# Arduino_Shield.net
KiCad netlist of a schematic drawn in EAGLE
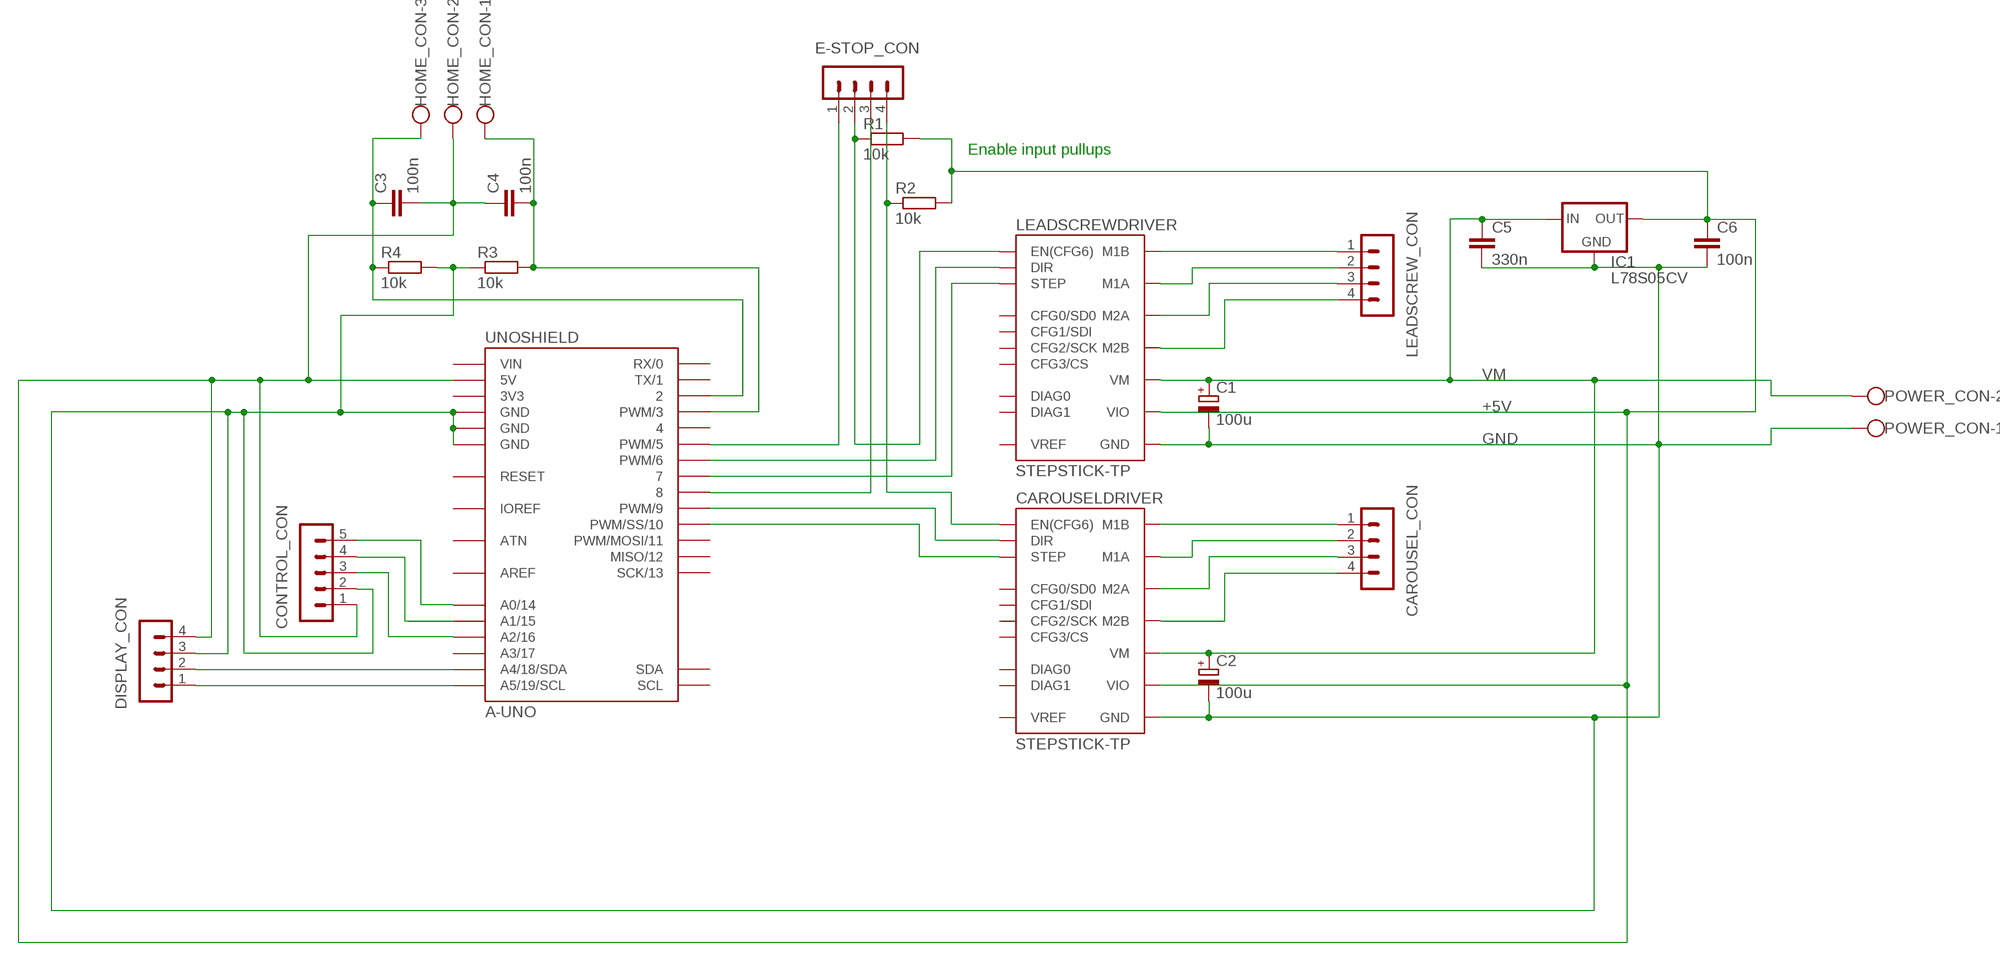
[diagram p0: schematic, sheet 1]

(export (version "E")
  (design (tool "Eeschema 10.0.6"))
  (components
    (comp (ref "C1")
      (value "100u")
      (footprint "eagle-import:E3,5-8")
      (libsource (lib "eagle-import") (part "CPOL-EUE3.5-8"))
    )
    (comp (ref "C2")
      (value "100u")
      (footprint "eagle-import:E3,5-8")
      (libsource (lib "eagle-import") (part "CPOL-EUE3.5-8"))
    )
    (comp (ref "C3")
      (value "100n")
      (footprint "eagle-import:C025-024X044")
      (libsource (lib "eagle-import") (part "C-EU025-024X044"))
    )
    (comp (ref "C4")
      (value "100n")
      (footprint "eagle-import:C025-024X044")
      (libsource (lib "eagle-import") (part "C-EU025-024X044"))
    )
    (comp (ref "C5")
      (value "330n")
      (footprint "eagle-import:C025-030X050")
      (libsource (lib "eagle-import") (part "C-EU025-030X050"))
    )
    (comp (ref "C6")
      (value "100n")
      (footprint "eagle-import:C025-030X050")
      (libsource (lib "eagle-import") (part "C-EU025-030X050"))
    )
    (comp (ref "CAROUSELDRIVER")
      (value "STEPSTICK-TP")
      (footprint "eagle-import:STEPSTICK_TP")
      (libsource (lib "eagle-import") (part "STEPSTICK-TP"))
    )
    (comp (ref "CAROUSEL_CON")
      (value "MA04-1")
      (footprint "eagle-import:MA04-1")
      (libsource (lib "eagle-import") (part "MA04-1"))
    )
    (comp (ref "CONTROL_CON")
      (value "MA05-1")
      (footprint "eagle-import:MA05-1")
      (libsource (lib "eagle-import") (part "MA05-1"))
    )
    (comp (ref "DISPLAY_CON")
      (value "MA04-1")
      (footprint "eagle-import:MA04-1")
      (libsource (lib "eagle-import") (part "MA04-1"))
    )
    (comp (ref "E-STOP_CON")
      (value "MA04-1")
      (footprint "eagle-import:MA04-1")
      (libsource (lib "eagle-import") (part "MA04-1"))
    )
    (comp (ref "HOME_CON")
      (value "W237-103")
      (footprint "eagle-import:W237-103")
      (fields (field (name "MPN") "237-103"))
      (libsource (lib "eagle-import") (part "W237-103"))
    )
    (comp (ref "IC1")
      (value "L78S05CV")
      (footprint "eagle-import:TO-220-STANDING")
      (fields (field (name "MF") "STMicroelectronics"))
      (libsource (lib "eagle-import") (part "L78S05CV"))
    )
    (comp (ref "LEADSCREWDRIVER")
      (value "STEPSTICK-TP")
      (footprint "eagle-import:STEPSTICK_TP")
      (libsource (lib "eagle-import") (part "STEPSTICK-TP"))
    )
    (comp (ref "LEADSCREW_CON")
      (value "MA04-1")
      (footprint "eagle-import:MA04-1")
      (libsource (lib "eagle-import") (part "MA04-1"))
    )
    (comp (ref "POWER_CON")
      (value "W237-102")
      (footprint "eagle-import:W237-102")
      (fields (field (name "MPN") "237-102"))
      (libsource (lib "eagle-import") (part "W237-102"))
    )
    (comp (ref "R1")
      (value "10k")
      (footprint "eagle-import:0207_12")
      (libsource (lib "eagle-import") (part "R-EU_0207/12"))
    )
    (comp (ref "R2")
      (value "10k")
      (footprint "eagle-import:0207_12")
      (libsource (lib "eagle-import") (part "R-EU_0207/12"))
    )
    (comp (ref "R3")
      (value "10k")
      (footprint "eagle-import:0207_10")
      (libsource (lib "eagle-import") (part "R-EU_0207/10"))
    )
    (comp (ref "R4")
      (value "10k")
      (footprint "eagle-import:0207_10")
      (libsource (lib "eagle-import") (part "R-EU_0207/10"))
    )
    (comp (ref "UNOSHIELD")
      (value "A-UNO")
      (footprint "eagle-import:A-UNO")
      (libsource (lib "eagle-import") (part "A-UNO"))
    )
  )
  (nets
    (net (code "1") (name "/+5V") (class "Default")
      (node (ref "C3") (pin "2") (pinfunction "2_2") (pintype "passive"))
      (node (ref "C4") (pin "1") (pinfunction "1_1") (pintype "passive"))
      (node (ref "C6") (pin "1") (pinfunction "1_1") (pintype "passive"))
      (node (ref "CAROUSELDRIVER") (pin "VIO") (pinfunction "VIO_VIO") (pintype "power_in"))
      (node (ref "CONTROL_CON") (pin "1") (pinfunction "1_1") (pintype "passive"))
      (node (ref "DISPLAY_CON") (pin "4") (pinfunction "4_4") (pintype "passive"))
      (node (ref "HOME_CON") (pin "2") (pinfunction "KL_2") (pintype "passive"))
      (node (ref "IC1") (pin "3") (pinfunction "OUT_3") (pintype "passive"))
      (node (ref "LEADSCREWDRIVER") (pin "VIO") (pinfunction "VIO_VIO") (pintype "power_in"))
      (node (ref "R1") (pin "2") (pinfunction "2_2") (pintype "passive"))
      (node (ref "R2") (pin "2") (pinfunction "2_2") (pintype "passive"))
      (node (ref "UNOSHIELD") (pin "5V") (pinfunction "5V_5V") (pintype "power_in"))
    )
    (net (code "2") (name "/3V3") (class "Default")
      (node (ref "UNOSHIELD") (pin "3V3") (pinfunction "3V3_3V3") (pintype "power_in"))
    )
    (net (code "3") (name "/AREF") (class "Default")
      (node (ref "UNOSHIELD") (pin "AREF") (pinfunction "AREF_AREF") (pintype "power_in"))
    )
    (net (code "4") (name "/GND") (class "Default")
      (node (ref "C1") (pin "-") (pinfunction "-_-") (pintype "passive"))
      (node (ref "C2") (pin "-") (pinfunction "-_-") (pintype "passive"))
      (node (ref "C5") (pin "2") (pinfunction "2_2") (pintype "passive"))
      (node (ref "C6") (pin "2") (pinfunction "2_2") (pintype "passive"))
      (node (ref "CAROUSELDRIVER") (pin "GND@1") (pinfunction "GND_GND@1") (pintype "power_in"))
      (node (ref "CAROUSELDRIVER") (pin "GND@2") (pinfunction "GND_GND@2") (pintype "power_in"))
      (node (ref "CONTROL_CON") (pin "2") (pinfunction "2_2") (pintype "passive"))
      (node (ref "DISPLAY_CON") (pin "3") (pinfunction "3_3") (pintype "passive"))
      (node (ref "IC1") (pin "2") (pinfunction "GND_2") (pintype "input"))
      (node (ref "LEADSCREWDRIVER") (pin "GND@1") (pinfunction "GND_GND@1") (pintype "power_in"))
      (node (ref "LEADSCREWDRIVER") (pin "GND@2") (pinfunction "GND_GND@2") (pintype "power_in"))
      (node (ref "POWER_CON") (pin "1") (pinfunction "KL_1") (pintype "passive"))
      (node (ref "R3") (pin "1") (pinfunction "1_1") (pintype "passive"))
      (node (ref "R4") (pin "2") (pinfunction "2_2") (pintype "passive"))
      (node (ref "UNOSHIELD") (pin "GND@1") (pinfunction "GND_GND@1") (pintype "power_in"))
      (node (ref "UNOSHIELD") (pin "GND@2") (pinfunction "GND_GND@2") (pintype "power_in"))
      (node (ref "UNOSHIELD") (pin "GND@3") (pinfunction "GND_GND@3") (pintype "power_in"))
    )
    (net (code "5") (name "/IOREF") (class "Default")
      (node (ref "UNOSHIELD") (pin "IOREF") (pinfunction "IOREF_IOREF") (pintype "power_in"))
    )
    (net (code "6") (name "/VIN") (class "Default")
      (node (ref "UNOSHIELD") (pin "VIN") (pinfunction "VIN_VIN") (pintype "power_in"))
    )
    (net (code "7") (name "/VM") (class "Default")
      (node (ref "C1") (pin "+") (pinfunction "+_+") (pintype "passive"))
      (node (ref "C2") (pin "+") (pinfunction "+_+") (pintype "passive"))
      (node (ref "C5") (pin "1") (pinfunction "1_1") (pintype "passive"))
      (node (ref "CAROUSELDRIVER") (pin "VM") (pinfunction "VM_VM") (pintype "power_in"))
      (node (ref "IC1") (pin "1") (pinfunction "IN_1") (pintype "input"))
      (node (ref "LEADSCREWDRIVER") (pin "VM") (pinfunction "VM_VM") (pintype "power_in"))
      (node (ref "POWER_CON") (pin "2") (pinfunction "KL_2") (pintype "passive"))
    )
    (net (code "8") (name "Net-(CAROUSELDRIVER-EN(CFG6))") (class "Default")
      (node (ref "CAROUSELDRIVER") (pin "EN") (pinfunction "EN(CFG6)_EN") (pintype "bidirectional"))
      (node (ref "E-STOP_CON") (pin "4") (pinfunction "4_4") (pintype "passive"))
      (node (ref "R2") (pin "1") (pinfunction "1_1") (pintype "passive"))
    )
    (net (code "9") (name "Net-(CAROUSELDRIVER-PadM1A)") (class "Default")
      (node (ref "CAROUSELDRIVER") (pin "M1A") (pinfunction "M1A_M1A") (pintype "output"))
      (node (ref "CAROUSEL_CON") (pin "2") (pinfunction "2_2") (pintype "passive"))
    )
    (net (code "10") (name "Net-(CAROUSELDRIVER-PadM1B)") (class "Default")
      (node (ref "CAROUSELDRIVER") (pin "M1B") (pinfunction "M1B_M1B") (pintype "output"))
      (node (ref "CAROUSEL_CON") (pin "1") (pinfunction "1_1") (pintype "passive"))
    )
    (net (code "11") (name "Net-(CAROUSELDRIVER-PadM2A)") (class "Default")
      (node (ref "CAROUSELDRIVER") (pin "M2A") (pinfunction "M2A_M2A") (pintype "output"))
      (node (ref "CAROUSEL_CON") (pin "3") (pinfunction "3_3") (pintype "passive"))
    )
    (net (code "12") (name "Net-(CAROUSELDRIVER-PadM2B)") (class "Default")
      (node (ref "CAROUSELDRIVER") (pin "M2B") (pinfunction "M2B_M2B") (pintype "output"))
      (node (ref "CAROUSEL_CON") (pin "4") (pinfunction "4_4") (pintype "passive"))
    )
    (net (code "13") (name "Net-(E-STOP_CON-Pad3)") (class "Default")
      (node (ref "E-STOP_CON") (pin "3") (pinfunction "3_3") (pintype "passive"))
      (node (ref "UNOSHIELD") (pin "8") (pinfunction "8_8") (pintype "bidirectional"))
    )
    (net (code "14") (name "Net-(HOME_CONA-KL)") (class "Default")
      (node (ref "C4") (pin "2") (pinfunction "2_2") (pintype "passive"))
      (node (ref "HOME_CON") (pin "1") (pinfunction "KL_1") (pintype "passive"))
      (node (ref "R3") (pin "2") (pinfunction "2_2") (pintype "passive"))
      (node (ref "UNOSHIELD") (pin "3") (pinfunction "PWM/3_3") (pintype "bidirectional"))
    )
    (net (code "15") (name "Net-(HOME_CONC-KL)") (class "Default")
      (node (ref "C3") (pin "1") (pinfunction "1_1") (pintype "passive"))
      (node (ref "HOME_CON") (pin "3") (pinfunction "KL_3") (pintype "passive"))
      (node (ref "R4") (pin "1") (pinfunction "1_1") (pintype "passive"))
      (node (ref "UNOSHIELD") (pin "2") (pinfunction "2_2") (pintype "bidirectional"))
    )
    (net (code "16") (name "Net-(LEADSCREWDRIVER-EN(CFG6))") (class "Default")
      (node (ref "E-STOP_CON") (pin "2") (pinfunction "2_2") (pintype "passive"))
      (node (ref "LEADSCREWDRIVER") (pin "EN") (pinfunction "EN(CFG6)_EN") (pintype "bidirectional"))
      (node (ref "R1") (pin "1") (pinfunction "1_1") (pintype "passive"))
    )
    (net (code "17") (name "Net-(LEADSCREWDRIVER-PadM1A)") (class "Default")
      (node (ref "LEADSCREWDRIVER") (pin "M1A") (pinfunction "M1A_M1A") (pintype "output"))
      (node (ref "LEADSCREW_CON") (pin "2") (pinfunction "2_2") (pintype "passive"))
    )
    (net (code "18") (name "Net-(LEADSCREWDRIVER-PadM1B)") (class "Default")
      (node (ref "LEADSCREWDRIVER") (pin "M1B") (pinfunction "M1B_M1B") (pintype "output"))
      (node (ref "LEADSCREW_CON") (pin "1") (pinfunction "1_1") (pintype "passive"))
    )
    (net (code "19") (name "Net-(LEADSCREWDRIVER-PadM2A)") (class "Default")
      (node (ref "LEADSCREWDRIVER") (pin "M2A") (pinfunction "M2A_M2A") (pintype "output"))
      (node (ref "LEADSCREW_CON") (pin "3") (pinfunction "3_3") (pintype "passive"))
    )
    (net (code "20") (name "Net-(LEADSCREWDRIVER-PadM2B)") (class "Default")
      (node (ref "LEADSCREWDRIVER") (pin "M2B") (pinfunction "M2B_M2B") (pintype "output"))
      (node (ref "LEADSCREW_CON") (pin "4") (pinfunction "4_4") (pintype "passive"))
    )
    (net (code "21") (name "Net-(LEADSCREWDRIVER-PadSTEP)") (class "Default")
      (node (ref "LEADSCREWDRIVER") (pin "STEP") (pinfunction "STEP_STEP") (pintype "bidirectional"))
      (node (ref "UNOSHIELD") (pin "7") (pinfunction "7_7") (pintype "bidirectional"))
    )
    (net (code "22") (name "Net-(UNOSHIELD-A0{slash}14)") (class "Default")
      (node (ref "CONTROL_CON") (pin "5") (pinfunction "5_5") (pintype "passive"))
      (node (ref "UNOSHIELD") (pin "A0") (pinfunction "A0/14_A0") (pintype "bidirectional"))
    )
    (net (code "23") (name "Net-(UNOSHIELD-A1{slash}15)") (class "Default")
      (node (ref "CONTROL_CON") (pin "4") (pinfunction "4_4") (pintype "passive"))
      (node (ref "UNOSHIELD") (pin "A1") (pinfunction "A1/15_A1") (pintype "bidirectional"))
    )
    (net (code "24") (name "Net-(UNOSHIELD-A2{slash}16)") (class "Default")
      (node (ref "CONTROL_CON") (pin "3") (pinfunction "3_3") (pintype "passive"))
      (node (ref "UNOSHIELD") (pin "A2") (pinfunction "A2/16_A2") (pintype "bidirectional"))
    )
    (net (code "25") (name "Net-(UNOSHIELD-A4{slash}18{slash}SDA)") (class "Default")
      (node (ref "DISPLAY_CON") (pin "2") (pinfunction "2_2") (pintype "passive"))
      (node (ref "UNOSHIELD") (pin "A4") (pinfunction "A4/18/SDA_A4") (pintype "bidirectional"))
    )
    (net (code "26") (name "Net-(UNOSHIELD-A5{slash}19{slash}SCL)") (class "Default")
      (node (ref "DISPLAY_CON") (pin "1") (pinfunction "1_1") (pintype "passive"))
      (node (ref "UNOSHIELD") (pin "A5") (pinfunction "A5/19/SCL_A5") (pintype "bidirectional"))
    )
    (net (code "27") (name "Net-(UNOSHIELD-PWM{slash}5)") (class "Default")
      (node (ref "E-STOP_CON") (pin "1") (pinfunction "1_1") (pintype "passive"))
      (node (ref "UNOSHIELD") (pin "5") (pinfunction "PWM/5_5") (pintype "bidirectional"))
    )
    (net (code "28") (name "Net-(UNOSHIELD-PWM{slash}6)") (class "Default")
      (node (ref "LEADSCREWDRIVER") (pin "DIR") (pinfunction "DIR_DIR") (pintype "bidirectional"))
      (node (ref "UNOSHIELD") (pin "6") (pinfunction "PWM/6_6") (pintype "bidirectional"))
    )
    (net (code "29") (name "Net-(UNOSHIELD-PWM{slash}9)") (class "Default")
      (node (ref "CAROUSELDRIVER") (pin "DIR") (pinfunction "DIR_DIR") (pintype "bidirectional"))
      (node (ref "UNOSHIELD") (pin "9") (pinfunction "PWM/9_9") (pintype "bidirectional"))
    )
    (net (code "30") (name "Net-(UNOSHIELD-PWM{slash}SS{slash}10)") (class "Default")
      (node (ref "CAROUSELDRIVER") (pin "STEP") (pinfunction "STEP_STEP") (pintype "bidirectional"))
      (node (ref "UNOSHIELD") (pin "10") (pinfunction "PWM/SS/10_10") (pintype "bidirectional"))
    )
    (net (code "31") (name "unconnected-(CAROUSELDRIVER-CFG0{slash}SD0-PadNC{slash}CFG0)") (class "Default")
      (node (ref "CAROUSELDRIVER") (pin "NC/CFG0") (pinfunction "CFG0/SD0_NC/CFG0") (pintype "bidirectional"))
    )
    (net (code "32") (name "unconnected-(CAROUSELDRIVER-CFG1{slash}SDI-PadCFG1)") (class "Default")
      (node (ref "CAROUSELDRIVER") (pin "CFG1") (pinfunction "CFG1/SDI_CFG1") (pintype "bidirectional"))
    )
    (net (code "33") (name "unconnected-(CAROUSELDRIVER-CFG2{slash}SCK-PadCFG2)") (class "Default")
      (node (ref "CAROUSELDRIVER") (pin "CFG2") (pinfunction "CFG2/SCK_CFG2") (pintype "bidirectional"))
    )
    (net (code "34") (name "unconnected-(CAROUSELDRIVER-CFG3{slash}CS-PadCFG3)") (class "Default")
      (node (ref "CAROUSELDRIVER") (pin "CFG3") (pinfunction "CFG3/CS_CFG3") (pintype "bidirectional"))
    )
    (net (code "35") (name "unconnected-(CAROUSELDRIVER-PadDIAG0)") (class "Default")
      (node (ref "CAROUSELDRIVER") (pin "DIAG0") (pinfunction "DIAG0_DIAG0") (pintype "bidirectional"))
    )
    (net (code "36") (name "unconnected-(CAROUSELDRIVER-PadDIAG1)") (class "Default")
      (node (ref "CAROUSELDRIVER") (pin "DIAG1") (pinfunction "DIAG1_DIAG1") (pintype "bidirectional"))
    )
    (net (code "37") (name "unconnected-(CAROUSELDRIVER-PadVREF)") (class "Default")
      (node (ref "CAROUSELDRIVER") (pin "VREF") (pinfunction "VREF_VREF") (pintype "passive"))
    )
    (net (code "38") (name "unconnected-(LEADSCREWDRIVER-CFG0{slash}SD0-PadNC{slash}CFG0)") (class "Default")
      (node (ref "LEADSCREWDRIVER") (pin "NC/CFG0") (pinfunction "CFG0/SD0_NC/CFG0") (pintype "bidirectional"))
    )
    (net (code "39") (name "unconnected-(LEADSCREWDRIVER-CFG1{slash}SDI-PadCFG1)") (class "Default")
      (node (ref "LEADSCREWDRIVER") (pin "CFG1") (pinfunction "CFG1/SDI_CFG1") (pintype "bidirectional"))
    )
    (net (code "40") (name "unconnected-(LEADSCREWDRIVER-CFG2{slash}SCK-PadCFG2)") (class "Default")
      (node (ref "LEADSCREWDRIVER") (pin "CFG2") (pinfunction "CFG2/SCK_CFG2") (pintype "bidirectional"))
    )
    (net (code "41") (name "unconnected-(LEADSCREWDRIVER-CFG3{slash}CS-PadCFG3)") (class "Default")
      (node (ref "LEADSCREWDRIVER") (pin "CFG3") (pinfunction "CFG3/CS_CFG3") (pintype "bidirectional"))
    )
    (net (code "42") (name "unconnected-(LEADSCREWDRIVER-PadDIAG0)") (class "Default")
      (node (ref "LEADSCREWDRIVER") (pin "DIAG0") (pinfunction "DIAG0_DIAG0") (pintype "bidirectional"))
    )
    (net (code "43") (name "unconnected-(LEADSCREWDRIVER-PadDIAG1)") (class "Default")
      (node (ref "LEADSCREWDRIVER") (pin "DIAG1") (pinfunction "DIAG1_DIAG1") (pintype "bidirectional"))
    )
    (net (code "44") (name "unconnected-(LEADSCREWDRIVER-PadVREF)") (class "Default")
      (node (ref "LEADSCREWDRIVER") (pin "VREF") (pinfunction "VREF_VREF") (pintype "passive"))
    )
    (net (code "45") (name "unconnected-(UNOSHIELD-A3{slash}17-PadA3)") (class "Default")
      (node (ref "UNOSHIELD") (pin "A3") (pinfunction "A3/17_A3") (pintype "bidirectional"))
    )
    (net (code "46") (name "unconnected-(UNOSHIELD-MISO{slash}12-Pad12)") (class "Default")
      (node (ref "UNOSHIELD") (pin "12") (pinfunction "MISO/12_12") (pintype "bidirectional"))
    )
    (net (code "47") (name "unconnected-(UNOSHIELD-PWM{slash}MOSI{slash}11-Pad11)") (class "Default")
      (node (ref "UNOSHIELD") (pin "11") (pinfunction "PWM/MOSI/11_11") (pintype "bidirectional"))
    )
    (net (code "48") (name "unconnected-(UNOSHIELD-Pad4)") (class "Default")
      (node (ref "UNOSHIELD") (pin "4") (pinfunction "4_4") (pintype "bidirectional"))
    )
    (net (code "49") (name "unconnected-(UNOSHIELD-PadATN)") (class "Default")
      (node (ref "UNOSHIELD") (pin "ATN") (pinfunction "ATN_ATN") (pintype "bidirectional"))
    )
    (net (code "50") (name "unconnected-(UNOSHIELD-PadSCL)") (class "Default")
      (node (ref "UNOSHIELD") (pin "SCL") (pinfunction "SCL_SCL") (pintype "bidirectional"))
    )
    (net (code "51") (name "unconnected-(UNOSHIELD-PadSDA)") (class "Default")
      (node (ref "UNOSHIELD") (pin "SDA") (pinfunction "SDA_SDA") (pintype "bidirectional"))
    )
    (net (code "52") (name "unconnected-(UNOSHIELD-RESET-PadRST)") (class "Default")
      (node (ref "UNOSHIELD") (pin "RST") (pinfunction "RESET_RST") (pintype "bidirectional"))
    )
    (net (code "53") (name "unconnected-(UNOSHIELD-RX{slash}0-Pad0)") (class "Default")
      (node (ref "UNOSHIELD") (pin "0") (pinfunction "RX/0_0") (pintype "bidirectional"))
    )
    (net (code "54") (name "unconnected-(UNOSHIELD-SCK{slash}13-Pad13)") (class "Default")
      (node (ref "UNOSHIELD") (pin "13") (pinfunction "SCK/13_13") (pintype "bidirectional"))
    )
    (net (code "55") (name "unconnected-(UNOSHIELD-TX{slash}1-Pad1)") (class "Default")
      (node (ref "UNOSHIELD") (pin "1") (pinfunction "TX/1_1") (pintype "bidirectional"))
    )
  )
)
